# CanTrans.net
KiCad netlist of a schematic drawn in Altium Designer
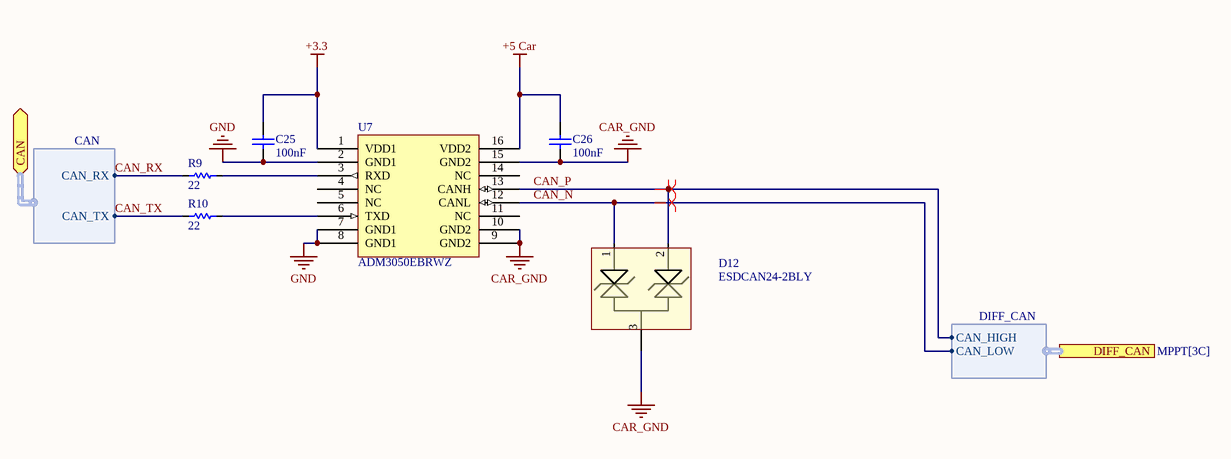
[diagram p0: CanTrans.SchDoc]

(export (version "E")
  (design (tool "Eeschema 10.0.6"))
  (components
    (comp (ref "C25")
      (value "100nF")
      (footprint "CAPC1608X90X40ML10T20")
      (description "Chip Capacitor, 0.1uF, +/- 10%, 50 V, 0603 (1608 Metric)")
      (fields (field (name "TOLERANCE") "10%") (field (name "Comment") "Capacitor 0.1uF +/-10% 50 V 0603"))
      (libsource (lib "University of Minnesota - Solar Vehicle Project") (part "Cap"))
    )
    (comp (ref "C26")
      (value "100nF")
      (footprint "CAPC1608X90X40ML10T20")
      (description "Chip Capacitor, 0.1uF, +/- 10%, 50 V, 0603 (1608 Metric)")
      (fields (field (name "TOLERANCE") "10%") (field (name "Comment") "Capacitor 0.1uF +/-10% 50 V 0603"))
      (libsource (lib "University of Minnesota - Solar Vehicle Project") (part "Cap"))
    )
    (comp (ref "D12")
      (value "ESDCAN24-2BLY")
      (footprint "SOT23-3")
      (description "ESD Suppressor TVS 24V Automotive 3-Pin SOT-23 T/R")
      (libsource (lib "University of Minnesota - Solar Vehicle Project") (part "D_MMBZ6V8AL,215"))
    )
    (comp (ref "R9")
      (value "22")
      (footprint "0603_RESISTOR")
      (description "RES 22 OHM 1/16W 1% 0603 SMD")
      (fields (field (name "TOLERANCE") "1%") (field (name "POWER") "62.5mW"))
      (libsource (lib "University of Minnesota - Solar Vehicle Project") (part "Symbol"))
    )
    (comp (ref "R10")
      (value "22")
      (footprint "0603_RESISTOR")
      (description "RES 22 OHM 1/16W 1% 0603 SMD")
      (fields (field (name "TOLERANCE") "1%") (field (name "POWER") "62.5mW"))
      (libsource (lib "University of Minnesota - Solar Vehicle Project") (part "Symbol"))
    )
    (comp (ref "U7")
      (value "ADM3050EBRWZ")
      (footprint "SOIC127P1030X265-16N")
      (description "MIL-STD-1553 Data Bus Transceiver, PDSO16. Isolated CANFD transceiver")
      (libsource (lib "University of Minnesota - Solar Vehicle Project") (part "ADM3050EBRWZ-Symbol-1"))
    )
  )
  (nets
    (net (code "3") (name "+3.3") (class "Default")
      (node (ref "C25") (pin "2") (pinfunction "2_2") (pintype "passive"))
      (node (ref "U7") (pin "1") (pinfunction "VDD1_1") (pintype "power_in"))
    )
    (net (code "4") (name "+5 Car") (class "Default")
      (node (ref "C26") (pin "1") (pinfunction "1_1") (pintype "passive"))
      (node (ref "U7") (pin "16") (pinfunction "VDD2_16") (pintype "power_in"))
    )
    (net (code "5") (name "/CAN_N") (class "Default")
      (node (ref "D12") (pin "1") (pinfunction "1_1") (pintype "passive"))
      (node (ref "U7") (pin "12") (pinfunction "CANL_12") (pintype "bidirectional"))
    )
    (net (code "6") (name "/CAN_P") (class "Default")
      (node (ref "D12") (pin "2") (pinfunction "2_2") (pintype "passive"))
      (node (ref "U7") (pin "13") (pinfunction "CANH_13") (pintype "bidirectional"))
    )
    (net (code "7") (name "/CAN_RX") (class "Default")
      (node (ref "R9") (pin "1") (pinfunction "1_1") (pintype "passive"))
    )
    (net (code "8") (name "/CAN_TX") (class "Default")
      (node (ref "R10") (pin "1") (pinfunction "1_1") (pintype "passive"))
    )
    (net (code "11") (name "CAR_GND") (class "Default")
      (node (ref "C26") (pin "2") (pinfunction "2_2") (pintype "passive"))
      (node (ref "D12") (pin "3") (pinfunction "3_3") (pintype "passive"))
      (node (ref "U7") (pin "10") (pinfunction "GND2_10") (pintype "power_in"))
      (node (ref "U7") (pin "15") (pinfunction "GND2_15") (pintype "power_in"))
      (node (ref "U7") (pin "9") (pinfunction "GND2_9") (pintype "power_in"))
    )
    (net (code "12") (name "GND") (class "Default")
      (node (ref "C25") (pin "1") (pinfunction "1_1") (pintype "passive"))
      (node (ref "U7") (pin "2") (pinfunction "GND1_2") (pintype "power_in"))
      (node (ref "U7") (pin "7") (pinfunction "GND1_7") (pintype "power_in"))
      (node (ref "U7") (pin "8") (pinfunction "GND1_8") (pintype "power_in"))
    )
    (net (code "13") (name "Net-(U7-RXD)") (class "Default")
      (node (ref "R9") (pin "2") (pinfunction "2_2") (pintype "passive"))
      (node (ref "U7") (pin "3") (pinfunction "RXD_3") (pintype "output"))
    )
    (net (code "14") (name "Net-(U7-TXD)") (class "Default")
      (node (ref "R10") (pin "2") (pinfunction "2_2") (pintype "passive"))
      (node (ref "U7") (pin "6") (pinfunction "TXD_6") (pintype "input"))
    )
    (net (code "15") (name "unconnected-(U7-NC-Pad4)") (class "Default")
      (node (ref "U7") (pin "4") (pinfunction "NC_4") (pintype "passive"))
    )
    (net (code "16") (name "unconnected-(U7-NC-Pad5)") (class "Default")
      (node (ref "U7") (pin "5") (pinfunction "NC_5") (pintype "passive"))
    )
    (net (code "17") (name "unconnected-(U7-NC-Pad11)") (class "Default")
      (node (ref "U7") (pin "11") (pinfunction "NC_11") (pintype "passive"))
    )
    (net (code "18") (name "unconnected-(U7-NC-Pad14)") (class "Default")
      (node (ref "U7") (pin "14") (pinfunction "NC_14") (pintype "passive"))
    )
  )
)
